# ZYNQ-Connecters.net
KiCad netlist of a schematic drawn in Altium Designer
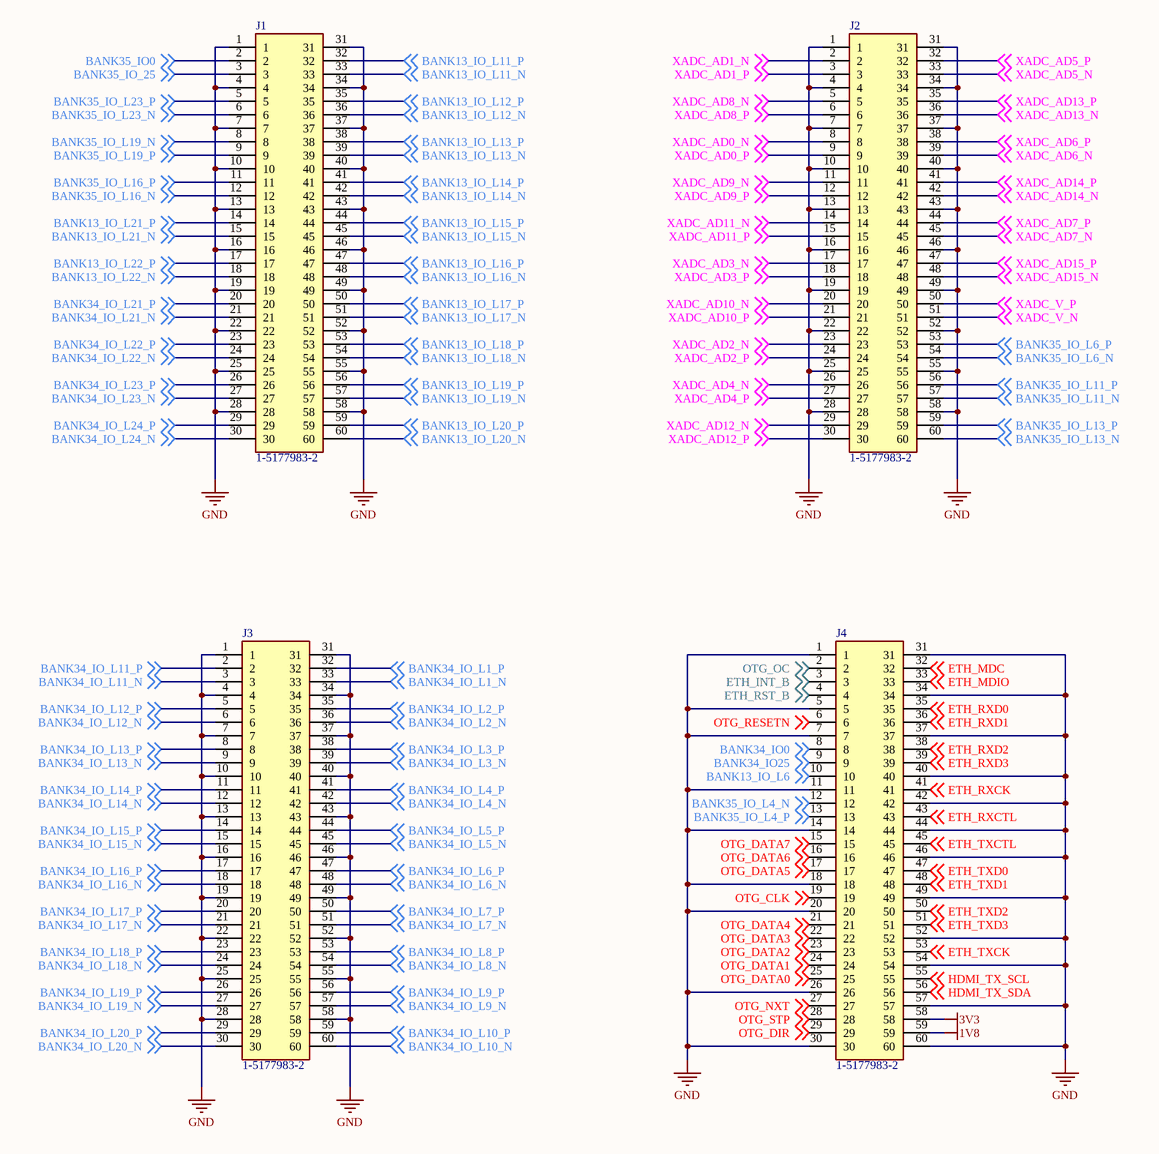
[diagram p0: ZYNQ-Connecters.SchDoc]

(export (version "E")
  (design (tool "Eeschema 10.0.6"))
  (components
    (comp (ref "J1")
      (value "1-5177983-2")
      (footprint "SamacSys:5177983-2")
      (description "Connector")
      (fields (field (name "MOUSER PART NUMBER") "571-1-5177983-2"))
      (libsource (lib "*") (part "1-5177983-2"))
    )
    (comp (ref "J2")
      (value "1-5177983-2")
      (footprint "SamacSys:5177983-2")
      (description "Connector")
      (fields (field (name "MOUSER PART NUMBER") "571-1-5177983-2"))
      (libsource (lib "*") (part "1-5177983-2"))
    )
    (comp (ref "J3")
      (value "1-5177983-2")
      (footprint "SamacSys:5177983-2")
      (description "Connector")
      (fields (field (name "MOUSER PART NUMBER") "571-1-5177983-2"))
      (libsource (lib "*") (part "1-5177983-2"))
    )
    (comp (ref "J4")
      (value "1-5177983-2")
      (footprint "SamacSys:5177983-2")
      (description "Connector")
      (fields (field (name "MOUSER PART NUMBER") "571-1-5177983-2"))
      (libsource (lib "*") (part "1-5177983-2"))
    )
  )
  (nets
    (net (code "1") (name "1V8") (class "Default")
      (node (ref "J4") (pin "59") (pinfunction "59_59") (pintype "passive"))
    )
    (net (code "2") (name "3V3") (class "Default")
      (node (ref "J4") (pin "58") (pinfunction "58_58") (pintype "passive"))
    )
    (net (code "3") (name "BANK13_IO_L6") (class "Default")
      (node (ref "J4") (pin "10") (pinfunction "10_10") (pintype "passive"))
    )
    (net (code "4") (name "BANK13_IO_L11_N") (class "Default")
      (node (ref "J1") (pin "33") (pinfunction "33_33") (pintype "passive"))
    )
    (net (code "5") (name "BANK13_IO_L11_P") (class "Default")
      (node (ref "J1") (pin "32") (pinfunction "32_32") (pintype "passive"))
    )
    (net (code "6") (name "BANK13_IO_L12_N") (class "Default")
      (node (ref "J1") (pin "36") (pinfunction "36_36") (pintype "passive"))
    )
    (net (code "7") (name "BANK13_IO_L12_P") (class "Default")
      (node (ref "J1") (pin "35") (pinfunction "35_35") (pintype "passive"))
    )
    (net (code "8") (name "BANK13_IO_L13_N") (class "Default")
      (node (ref "J1") (pin "39") (pinfunction "39_39") (pintype "passive"))
    )
    (net (code "9") (name "BANK13_IO_L13_P") (class "Default")
      (node (ref "J1") (pin "38") (pinfunction "38_38") (pintype "passive"))
    )
    (net (code "10") (name "BANK13_IO_L14_N") (class "Default")
      (node (ref "J1") (pin "42") (pinfunction "42_42") (pintype "passive"))
    )
    (net (code "11") (name "BANK13_IO_L14_P") (class "Default")
      (node (ref "J1") (pin "41") (pinfunction "41_41") (pintype "passive"))
    )
    (net (code "12") (name "BANK13_IO_L15_N") (class "Default")
      (node (ref "J1") (pin "45") (pinfunction "45_45") (pintype "passive"))
    )
    (net (code "13") (name "BANK13_IO_L15_P") (class "Default")
      (node (ref "J1") (pin "44") (pinfunction "44_44") (pintype "passive"))
    )
    (net (code "14") (name "BANK13_IO_L16_N") (class "Default")
      (node (ref "J1") (pin "48") (pinfunction "48_48") (pintype "passive"))
    )
    (net (code "15") (name "BANK13_IO_L16_P") (class "Default")
      (node (ref "J1") (pin "47") (pinfunction "47_47") (pintype "passive"))
    )
    (net (code "16") (name "BANK13_IO_L17_N") (class "Default")
      (node (ref "J1") (pin "51") (pinfunction "51_51") (pintype "passive"))
    )
    (net (code "17") (name "BANK13_IO_L17_P") (class "Default")
      (node (ref "J1") (pin "50") (pinfunction "50_50") (pintype "passive"))
    )
    (net (code "18") (name "BANK13_IO_L18_N") (class "Default")
      (node (ref "J1") (pin "54") (pinfunction "54_54") (pintype "passive"))
    )
    (net (code "19") (name "BANK13_IO_L18_P") (class "Default")
      (node (ref "J1") (pin "53") (pinfunction "53_53") (pintype "passive"))
    )
    (net (code "20") (name "BANK13_IO_L19_N") (class "Default")
      (node (ref "J1") (pin "57") (pinfunction "57_57") (pintype "passive"))
    )
    (net (code "21") (name "BANK13_IO_L19_P") (class "Default")
      (node (ref "J1") (pin "56") (pinfunction "56_56") (pintype "passive"))
    )
    (net (code "22") (name "BANK13_IO_L20_N") (class "Default")
      (node (ref "J1") (pin "60") (pinfunction "60_60") (pintype "passive"))
    )
    (net (code "23") (name "BANK13_IO_L20_P") (class "Default")
      (node (ref "J1") (pin "59") (pinfunction "59_59") (pintype "passive"))
    )
    (net (code "24") (name "BANK13_IO_L21_N") (class "Default")
      (node (ref "J1") (pin "15") (pinfunction "15_15") (pintype "passive"))
    )
    (net (code "25") (name "BANK13_IO_L21_P") (class "Default")
      (node (ref "J1") (pin "14") (pinfunction "14_14") (pintype "passive"))
    )
    (net (code "26") (name "BANK13_IO_L22_N") (class "Default")
      (node (ref "J1") (pin "18") (pinfunction "18_18") (pintype "passive"))
    )
    (net (code "27") (name "BANK13_IO_L22_P") (class "Default")
      (node (ref "J1") (pin "17") (pinfunction "17_17") (pintype "passive"))
    )
    (net (code "28") (name "BANK34_IO0") (class "Default")
      (node (ref "J4") (pin "8") (pinfunction "8_8") (pintype "passive"))
    )
    (net (code "29") (name "BANK34_IO25") (class "Default")
      (node (ref "J4") (pin "9") (pinfunction "9_9") (pintype "passive"))
    )
    (net (code "30") (name "BANK34_IO_L1_N") (class "Default")
      (node (ref "J3") (pin "33") (pinfunction "33_33") (pintype "passive"))
    )
    (net (code "31") (name "BANK34_IO_L1_P") (class "Default")
      (node (ref "J3") (pin "32") (pinfunction "32_32") (pintype "passive"))
    )
    (net (code "32") (name "BANK34_IO_L2_N") (class "Default")
      (node (ref "J3") (pin "36") (pinfunction "36_36") (pintype "passive"))
    )
    (net (code "33") (name "BANK34_IO_L2_P") (class "Default")
      (node (ref "J3") (pin "35") (pinfunction "35_35") (pintype "passive"))
    )
    (net (code "34") (name "BANK34_IO_L3_N") (class "Default")
      (node (ref "J3") (pin "39") (pinfunction "39_39") (pintype "passive"))
    )
    (net (code "35") (name "BANK34_IO_L3_P") (class "Default")
      (node (ref "J3") (pin "38") (pinfunction "38_38") (pintype "passive"))
    )
    (net (code "36") (name "BANK34_IO_L4_N") (class "Default")
      (node (ref "J3") (pin "42") (pinfunction "42_42") (pintype "passive"))
    )
    (net (code "37") (name "BANK34_IO_L4_P") (class "Default")
      (node (ref "J3") (pin "41") (pinfunction "41_41") (pintype "passive"))
    )
    (net (code "38") (name "BANK34_IO_L5_N") (class "Default")
      (node (ref "J3") (pin "45") (pinfunction "45_45") (pintype "passive"))
    )
    (net (code "39") (name "BANK34_IO_L5_P") (class "Default")
      (node (ref "J3") (pin "44") (pinfunction "44_44") (pintype "passive"))
    )
    (net (code "40") (name "BANK34_IO_L6_N") (class "Default")
      (node (ref "J3") (pin "48") (pinfunction "48_48") (pintype "passive"))
    )
    (net (code "41") (name "BANK34_IO_L6_P") (class "Default")
      (node (ref "J3") (pin "47") (pinfunction "47_47") (pintype "passive"))
    )
    (net (code "42") (name "BANK34_IO_L7_N") (class "Default")
      (node (ref "J3") (pin "51") (pinfunction "51_51") (pintype "passive"))
    )
    (net (code "43") (name "BANK34_IO_L7_P") (class "Default")
      (node (ref "J3") (pin "50") (pinfunction "50_50") (pintype "passive"))
    )
    (net (code "44") (name "BANK34_IO_L8_N") (class "Default")
      (node (ref "J3") (pin "54") (pinfunction "54_54") (pintype "passive"))
    )
    (net (code "45") (name "BANK34_IO_L8_P") (class "Default")
      (node (ref "J3") (pin "53") (pinfunction "53_53") (pintype "passive"))
    )
    (net (code "46") (name "BANK34_IO_L9_N") (class "Default")
      (node (ref "J3") (pin "57") (pinfunction "57_57") (pintype "passive"))
    )
    (net (code "47") (name "BANK34_IO_L9_P") (class "Default")
      (node (ref "J3") (pin "56") (pinfunction "56_56") (pintype "passive"))
    )
    (net (code "48") (name "BANK34_IO_L10_N") (class "Default")
      (node (ref "J3") (pin "60") (pinfunction "60_60") (pintype "passive"))
    )
    (net (code "49") (name "BANK34_IO_L10_P") (class "Default")
      (node (ref "J3") (pin "59") (pinfunction "59_59") (pintype "passive"))
    )
    (net (code "50") (name "BANK34_IO_L11_N") (class "Default")
      (node (ref "J3") (pin "3") (pinfunction "3_3") (pintype "passive"))
    )
    (net (code "51") (name "BANK34_IO_L11_P") (class "Default")
      (node (ref "J3") (pin "2") (pinfunction "2_2") (pintype "passive"))
    )
    (net (code "52") (name "BANK34_IO_L12_N") (class "Default")
      (node (ref "J3") (pin "6") (pinfunction "6_6") (pintype "passive"))
    )
    (net (code "53") (name "BANK34_IO_L12_P") (class "Default")
      (node (ref "J3") (pin "5") (pinfunction "5_5") (pintype "passive"))
    )
    (net (code "54") (name "BANK34_IO_L13_N") (class "Default")
      (node (ref "J3") (pin "9") (pinfunction "9_9") (pintype "passive"))
    )
    (net (code "55") (name "BANK34_IO_L13_P") (class "Default")
      (node (ref "J3") (pin "8") (pinfunction "8_8") (pintype "passive"))
    )
    (net (code "56") (name "BANK34_IO_L14_N") (class "Default")
      (node (ref "J3") (pin "12") (pinfunction "12_12") (pintype "passive"))
    )
    (net (code "57") (name "BANK34_IO_L14_P") (class "Default")
      (node (ref "J3") (pin "11") (pinfunction "11_11") (pintype "passive"))
    )
    (net (code "58") (name "BANK34_IO_L15_N") (class "Default")
      (node (ref "J3") (pin "15") (pinfunction "15_15") (pintype "passive"))
    )
    (net (code "59") (name "BANK34_IO_L15_P") (class "Default")
      (node (ref "J3") (pin "14") (pinfunction "14_14") (pintype "passive"))
    )
    (net (code "60") (name "BANK34_IO_L16_N") (class "Default")
      (node (ref "J3") (pin "18") (pinfunction "18_18") (pintype "passive"))
    )
    (net (code "61") (name "BANK34_IO_L16_P") (class "Default")
      (node (ref "J3") (pin "17") (pinfunction "17_17") (pintype "passive"))
    )
    (net (code "62") (name "BANK34_IO_L17_N") (class "Default")
      (node (ref "J3") (pin "21") (pinfunction "21_21") (pintype "passive"))
    )
    (net (code "63") (name "BANK34_IO_L17_P") (class "Default")
      (node (ref "J3") (pin "20") (pinfunction "20_20") (pintype "passive"))
    )
    (net (code "64") (name "BANK34_IO_L18_N") (class "Default")
      (node (ref "J3") (pin "24") (pinfunction "24_24") (pintype "passive"))
    )
    (net (code "65") (name "BANK34_IO_L18_P") (class "Default")
      (node (ref "J3") (pin "23") (pinfunction "23_23") (pintype "passive"))
    )
    (net (code "66") (name "BANK34_IO_L19_N") (class "Default")
      (node (ref "J3") (pin "27") (pinfunction "27_27") (pintype "passive"))
    )
    (net (code "67") (name "BANK34_IO_L19_P") (class "Default")
      (node (ref "J3") (pin "26") (pinfunction "26_26") (pintype "passive"))
    )
    (net (code "68") (name "BANK34_IO_L20_N") (class "Default")
      (node (ref "J3") (pin "30") (pinfunction "30_30") (pintype "passive"))
    )
    (net (code "69") (name "BANK34_IO_L20_P") (class "Default")
      (node (ref "J3") (pin "29") (pinfunction "29_29") (pintype "passive"))
    )
    (net (code "70") (name "BANK34_IO_L21_N") (class "Default")
      (node (ref "J1") (pin "21") (pinfunction "21_21") (pintype "passive"))
    )
    (net (code "71") (name "BANK34_IO_L21_P") (class "Default")
      (node (ref "J1") (pin "20") (pinfunction "20_20") (pintype "passive"))
    )
    (net (code "72") (name "BANK34_IO_L22_N") (class "Default")
      (node (ref "J1") (pin "24") (pinfunction "24_24") (pintype "passive"))
    )
    (net (code "73") (name "BANK34_IO_L22_P") (class "Default")
      (node (ref "J1") (pin "23") (pinfunction "23_23") (pintype "passive"))
    )
    (net (code "74") (name "BANK34_IO_L23_N") (class "Default")
      (node (ref "J1") (pin "27") (pinfunction "27_27") (pintype "passive"))
    )
    (net (code "75") (name "BANK34_IO_L23_P") (class "Default")
      (node (ref "J1") (pin "26") (pinfunction "26_26") (pintype "passive"))
    )
    (net (code "76") (name "BANK34_IO_L24_N") (class "Default")
      (node (ref "J1") (pin "30") (pinfunction "30_30") (pintype "passive"))
    )
    (net (code "77") (name "BANK34_IO_L24_P") (class "Default")
      (node (ref "J1") (pin "29") (pinfunction "29_29") (pintype "passive"))
    )
    (net (code "78") (name "BANK35_IO0") (class "Default")
      (node (ref "J1") (pin "2") (pinfunction "2_2") (pintype "passive"))
    )
    (net (code "79") (name "BANK35_IO_25") (class "Default")
      (node (ref "J1") (pin "3") (pinfunction "3_3") (pintype "passive"))
    )
    (net (code "80") (name "BANK35_IO_L4_N") (class "Default")
      (node (ref "J4") (pin "12") (pinfunction "12_12") (pintype "passive"))
    )
    (net (code "81") (name "BANK35_IO_L4_P") (class "Default")
      (node (ref "J4") (pin "13") (pinfunction "13_13") (pintype "passive"))
    )
    (net (code "82") (name "BANK35_IO_L6_N") (class "Default")
      (node (ref "J2") (pin "54") (pinfunction "54_54") (pintype "passive"))
    )
    (net (code "83") (name "BANK35_IO_L6_P") (class "Default")
      (node (ref "J2") (pin "53") (pinfunction "53_53") (pintype "passive"))
    )
    (net (code "84") (name "BANK35_IO_L11_N") (class "Default")
      (node (ref "J2") (pin "57") (pinfunction "57_57") (pintype "passive"))
    )
    (net (code "85") (name "BANK35_IO_L11_P") (class "Default")
      (node (ref "J2") (pin "56") (pinfunction "56_56") (pintype "passive"))
    )
    (net (code "86") (name "BANK35_IO_L13_N") (class "Default")
      (node (ref "J2") (pin "60") (pinfunction "60_60") (pintype "passive"))
    )
    (net (code "87") (name "BANK35_IO_L13_P") (class "Default")
      (node (ref "J2") (pin "59") (pinfunction "59_59") (pintype "passive"))
    )
    (net (code "88") (name "BANK35_IO_L16_N") (class "Default")
      (node (ref "J1") (pin "12") (pinfunction "12_12") (pintype "passive"))
    )
    (net (code "89") (name "BANK35_IO_L16_P") (class "Default")
      (node (ref "J1") (pin "11") (pinfunction "11_11") (pintype "passive"))
    )
    (net (code "90") (name "BANK35_IO_L19_N") (class "Default")
      (node (ref "J1") (pin "8") (pinfunction "8_8") (pintype "passive"))
    )
    (net (code "91") (name "BANK35_IO_L19_P") (class "Default")
      (node (ref "J1") (pin "9") (pinfunction "9_9") (pintype "passive"))
    )
    (net (code "92") (name "BANK35_IO_L23_N") (class "Default")
      (node (ref "J1") (pin "6") (pinfunction "6_6") (pintype "passive"))
    )
    (net (code "93") (name "BANK35_IO_L23_P") (class "Default")
      (node (ref "J1") (pin "5") (pinfunction "5_5") (pintype "passive"))
    )
    (net (code "94") (name "ETH_INT_B") (class "Default")
      (node (ref "J4") (pin "3") (pinfunction "3_3") (pintype "passive"))
    )
    (net (code "95") (name "ETH_MDC") (class "Default")
      (node (ref "J4") (pin "32") (pinfunction "32_32") (pintype "passive"))
    )
    (net (code "96") (name "ETH_MDIO") (class "Default")
      (node (ref "J4") (pin "33") (pinfunction "33_33") (pintype "passive"))
    )
    (net (code "97") (name "ETH_RST_B") (class "Default")
      (node (ref "J4") (pin "4") (pinfunction "4_4") (pintype "passive"))
    )
    (net (code "98") (name "ETH_RXCK") (class "Default")
      (node (ref "J4") (pin "41") (pinfunction "41_41") (pintype "passive"))
    )
    (net (code "99") (name "ETH_RXCTL") (class "Default")
      (node (ref "J4") (pin "43") (pinfunction "43_43") (pintype "passive"))
    )
    (net (code "100") (name "ETH_RXD0") (class "Default")
      (node (ref "J4") (pin "35") (pinfunction "35_35") (pintype "passive"))
    )
    (net (code "101") (name "ETH_RXD1") (class "Default")
      (node (ref "J4") (pin "36") (pinfunction "36_36") (pintype "passive"))
    )
    (net (code "102") (name "ETH_RXD2") (class "Default")
      (node (ref "J4") (pin "38") (pinfunction "38_38") (pintype "passive"))
    )
    (net (code "103") (name "ETH_RXD3") (class "Default")
      (node (ref "J4") (pin "39") (pinfunction "39_39") (pintype "passive"))
    )
    (net (code "104") (name "ETH_TXCK") (class "Default")
      (node (ref "J4") (pin "53") (pinfunction "53_53") (pintype "passive"))
    )
    (net (code "105") (name "ETH_TXCTL") (class "Default")
      (node (ref "J4") (pin "45") (pinfunction "45_45") (pintype "passive"))
    )
    (net (code "106") (name "ETH_TXD0") (class "Default")
      (node (ref "J4") (pin "47") (pinfunction "47_47") (pintype "passive"))
    )
    (net (code "107") (name "ETH_TXD1") (class "Default")
      (node (ref "J4") (pin "48") (pinfunction "48_48") (pintype "passive"))
    )
    (net (code "108") (name "ETH_TXD2") (class "Default")
      (node (ref "J4") (pin "50") (pinfunction "50_50") (pintype "passive"))
    )
    (net (code "109") (name "ETH_TXD3") (class "Default")
      (node (ref "J4") (pin "51") (pinfunction "51_51") (pintype "passive"))
    )
    (net (code "110") (name "GND") (class "Default")
      (node (ref "J1") (pin "1") (pinfunction "1_1") (pintype "passive"))
      (node (ref "J1") (pin "10") (pinfunction "10_10") (pintype "passive"))
      (node (ref "J1") (pin "13") (pinfunction "13_13") (pintype "passive"))
      (node (ref "J1") (pin "16") (pinfunction "16_16") (pintype "passive"))
      (node (ref "J1") (pin "19") (pinfunction "19_19") (pintype "passive"))
      (node (ref "J1") (pin "22") (pinfunction "22_22") (pintype "passive"))
      (node (ref "J1") (pin "25") (pinfunction "25_25") (pintype "passive"))
      (node (ref "J1") (pin "28") (pinfunction "28_28") (pintype "passive"))
      (node (ref "J1") (pin "31") (pinfunction "31_31") (pintype "passive"))
      (node (ref "J1") (pin "34") (pinfunction "34_34") (pintype "passive"))
      (node (ref "J1") (pin "37") (pinfunction "37_37") (pintype "passive"))
      (node (ref "J1") (pin "4") (pinfunction "4_4") (pintype "passive"))
      (node (ref "J1") (pin "40") (pinfunction "40_40") (pintype "passive"))
      (node (ref "J1") (pin "43") (pinfunction "43_43") (pintype "passive"))
      (node (ref "J1") (pin "46") (pinfunction "46_46") (pintype "passive"))
      (node (ref "J1") (pin "49") (pinfunction "49_49") (pintype "passive"))
      (node (ref "J1") (pin "52") (pinfunction "52_52") (pintype "passive"))
      (node (ref "J1") (pin "55") (pinfunction "55_55") (pintype "passive"))
      (node (ref "J1") (pin "58") (pinfunction "58_58") (pintype "passive"))
      (node (ref "J1") (pin "7") (pinfunction "7_7") (pintype "passive"))
      (node (ref "J2") (pin "1") (pinfunction "1_1") (pintype "passive"))
      (node (ref "J2") (pin "10") (pinfunction "10_10") (pintype "passive"))
      (node (ref "J2") (pin "13") (pinfunction "13_13") (pintype "passive"))
      (node (ref "J2") (pin "16") (pinfunction "16_16") (pintype "passive"))
      (node (ref "J2") (pin "19") (pinfunction "19_19") (pintype "passive"))
      (node (ref "J2") (pin "22") (pinfunction "22_22") (pintype "passive"))
      (node (ref "J2") (pin "25") (pinfunction "25_25") (pintype "passive"))
      (node (ref "J2") (pin "28") (pinfunction "28_28") (pintype "passive"))
      (node (ref "J2") (pin "31") (pinfunction "31_31") (pintype "passive"))
      (node (ref "J2") (pin "34") (pinfunction "34_34") (pintype "passive"))
      (node (ref "J2") (pin "37") (pinfunction "37_37") (pintype "passive"))
      (node (ref "J2") (pin "4") (pinfunction "4_4") (pintype "passive"))
      (node (ref "J2") (pin "40") (pinfunction "40_40") (pintype "passive"))
      (node (ref "J2") (pin "43") (pinfunction "43_43") (pintype "passive"))
      (node (ref "J2") (pin "46") (pinfunction "46_46") (pintype "passive"))
      (node (ref "J2") (pin "49") (pinfunction "49_49") (pintype "passive"))
      (node (ref "J2") (pin "52") (pinfunction "52_52") (pintype "passive"))
      (node (ref "J2") (pin "55") (pinfunction "55_55") (pintype "passive"))
      (node (ref "J2") (pin "58") (pinfunction "58_58") (pintype "passive"))
      (node (ref "J2") (pin "7") (pinfunction "7_7") (pintype "passive"))
      (node (ref "J3") (pin "1") (pinfunction "1_1") (pintype "passive"))
      (node (ref "J3") (pin "10") (pinfunction "10_10") (pintype "passive"))
      (node (ref "J3") (pin "13") (pinfunction "13_13") (pintype "passive"))
      (node (ref "J3") (pin "16") (pinfunction "16_16") (pintype "passive"))
      (node (ref "J3") (pin "19") (pinfunction "19_19") (pintype "passive"))
      (node (ref "J3") (pin "22") (pinfunction "22_22") (pintype "passive"))
      (node (ref "J3") (pin "25") (pinfunction "25_25") (pintype "passive"))
      (node (ref "J3") (pin "28") (pinfunction "28_28") (pintype "passive"))
      (node (ref "J3") (pin "31") (pinfunction "31_31") (pintype "passive"))
      (node (ref "J3") (pin "34") (pinfunction "34_34") (pintype "passive"))
      (node (ref "J3") (pin "37") (pinfunction "37_37") (pintype "passive"))
      (node (ref "J3") (pin "4") (pinfunction "4_4") (pintype "passive"))
      (node (ref "J3") (pin "40") (pinfunction "40_40") (pintype "passive"))
      (node (ref "J3") (pin "43") (pinfunction "43_43") (pintype "passive"))
      (node (ref "J3") (pin "46") (pinfunction "46_46") (pintype "passive"))
      (node (ref "J3") (pin "49") (pinfunction "49_49") (pintype "passive"))
      (node (ref "J3") (pin "52") (pinfunction "52_52") (pintype "passive"))
      (node (ref "J3") (pin "55") (pinfunction "55_55") (pintype "passive"))
      (node (ref "J3") (pin "58") (pinfunction "58_58") (pintype "passive"))
      (node (ref "J3") (pin "7") (pinfunction "7_7") (pintype "passive"))
      (node (ref "J4") (pin "1") (pinfunction "1_1") (pintype "passive"))
      (node (ref "J4") (pin "11") (pinfunction "11_11") (pintype "passive"))
      (node (ref "J4") (pin "14") (pinfunction "14_14") (pintype "passive"))
      (node (ref "J4") (pin "18") (pinfunction "18_18") (pintype "passive"))
      (node (ref "J4") (pin "20") (pinfunction "20_20") (pintype "passive"))
      (node (ref "J4") (pin "26") (pinfunction "26_26") (pintype "passive"))
      (node (ref "J4") (pin "30") (pinfunction "30_30") (pintype "passive"))
      (node (ref "J4") (pin "31") (pinfunction "31_31") (pintype "passive"))
      (node (ref "J4") (pin "34") (pinfunction "34_34") (pintype "passive"))
      (node (ref "J4") (pin "37") (pinfunction "37_37") (pintype "passive"))
      (node (ref "J4") (pin "40") (pinfunction "40_40") (pintype "passive"))
      (node (ref "J4") (pin "42") (pinfunction "42_42") (pintype "passive"))
      (node (ref "J4") (pin "44") (pinfunction "44_44") (pintype "passive"))
      (node (ref "J4") (pin "46") (pinfunction "46_46") (pintype "passive"))
      (node (ref "J4") (pin "49") (pinfunction "49_49") (pintype "passive"))
      (node (ref "J4") (pin "5") (pinfunction "5_5") (pintype "passive"))
      (node (ref "J4") (pin "52") (pinfunction "52_52") (pintype "passive"))
      (node (ref "J4") (pin "54") (pinfunction "54_54") (pintype "passive"))
      (node (ref "J4") (pin "57") (pinfunction "57_57") (pintype "passive"))
      (node (ref "J4") (pin "60") (pinfunction "60_60") (pintype "passive"))
      (node (ref "J4") (pin "7") (pinfunction "7_7") (pintype "passive"))
    )
    (net (code "111") (name "HDMI_TX_SCL") (class "Default")
      (node (ref "J4") (pin "55") (pinfunction "55_55") (pintype "passive"))
    )
    (net (code "112") (name "HDMI_TX_SDA") (class "Default")
      (node (ref "J4") (pin "56") (pinfunction "56_56") (pintype "passive"))
    )
    (net (code "113") (name "OTG_CLK") (class "Default")
      (node (ref "J4") (pin "19") (pinfunction "19_19") (pintype "passive"))
    )
    (net (code "114") (name "OTG_DATA0") (class "Default")
      (node (ref "J4") (pin "25") (pinfunction "25_25") (pintype "passive"))
    )
    (net (code "115") (name "OTG_DATA1") (class "Default")
      (node (ref "J4") (pin "24") (pinfunction "24_24") (pintype "passive"))
    )
    (net (code "116") (name "OTG_DATA2") (class "Default")
      (node (ref "J4") (pin "23") (pinfunction "23_23") (pintype "passive"))
    )
    (net (code "117") (name "OTG_DATA3") (class "Default")
      (node (ref "J4") (pin "22") (pinfunction "22_22") (pintype "passive"))
    )
    (net (code "118") (name "OTG_DATA4") (class "Default")
      (node (ref "J4") (pin "21") (pinfunction "21_21") (pintype "passive"))
    )
    (net (code "119") (name "OTG_DATA5") (class "Default")
      (node (ref "J4") (pin "17") (pinfunction "17_17") (pintype "passive"))
    )
    (net (code "120") (name "OTG_DATA6") (class "Default")
      (node (ref "J4") (pin "16") (pinfunction "16_16") (pintype "passive"))
    )
    (net (code "121") (name "OTG_DATA7") (class "Default")
      (node (ref "J4") (pin "15") (pinfunction "15_15") (pintype "passive"))
    )
    (net (code "122") (name "OTG_DIR") (class "Default")
      (node (ref "J4") (pin "29") (pinfunction "29_29") (pintype "passive"))
    )
    (net (code "123") (name "OTG_NXT") (class "Default")
      (node (ref "J4") (pin "27") (pinfunction "27_27") (pintype "passive"))
    )
    (net (code "124") (name "OTG_OC") (class "Default")
      (node (ref "J4") (pin "2") (pinfunction "2_2") (pintype "passive"))
    )
    (net (code "125") (name "OTG_RESETN") (class "Default")
      (node (ref "J4") (pin "6") (pinfunction "6_6") (pintype "passive"))
    )
    (net (code "126") (name "OTG_STP") (class "Default")
      (node (ref "J4") (pin "28") (pinfunction "28_28") (pintype "passive"))
    )
    (net (code "127") (name "XADC_AD0_N") (class "Default")
      (node (ref "J2") (pin "8") (pinfunction "8_8") (pintype "passive"))
    )
    (net (code "128") (name "XADC_AD0_P") (class "Default")
      (node (ref "J2") (pin "9") (pinfunction "9_9") (pintype "passive"))
    )
    (net (code "129") (name "XADC_AD1_N") (class "Default")
      (node (ref "J2") (pin "2") (pinfunction "2_2") (pintype "passive"))
    )
    (net (code "130") (name "XADC_AD1_P") (class "Default")
      (node (ref "J2") (pin "3") (pinfunction "3_3") (pintype "passive"))
    )
    (net (code "131") (name "XADC_AD2_N") (class "Default")
      (node (ref "J2") (pin "23") (pinfunction "23_23") (pintype "passive"))
    )
    (net (code "132") (name "XADC_AD2_P") (class "Default")
      (node (ref "J2") (pin "24") (pinfunction "24_24") (pintype "passive"))
    )
    (net (code "133") (name "XADC_AD3_N") (class "Default")
      (node (ref "J2") (pin "17") (pinfunction "17_17") (pintype "passive"))
    )
    (net (code "134") (name "XADC_AD3_P") (class "Default")
      (node (ref "J2") (pin "18") (pinfunction "18_18") (pintype "passive"))
    )
    (net (code "135") (name "XADC_AD4_N") (class "Default")
      (node (ref "J2") (pin "26") (pinfunction "26_26") (pintype "passive"))
    )
    (net (code "136") (name "XADC_AD4_P") (class "Default")
      (node (ref "J2") (pin "27") (pinfunction "27_27") (pintype "passive"))
    )
    (net (code "137") (name "XADC_AD5_N") (class "Default")
      (node (ref "J2") (pin "33") (pinfunction "33_33") (pintype "passive"))
    )
    (net (code "138") (name "XADC_AD5_P") (class "Default")
      (node (ref "J2") (pin "32") (pinfunction "32_32") (pintype "passive"))
    )
    (net (code "139") (name "XADC_AD6_N") (class "Default")
      (node (ref "J2") (pin "39") (pinfunction "39_39") (pintype "passive"))
    )
    (net (code "140") (name "XADC_AD6_P") (class "Default")
      (node (ref "J2") (pin "38") (pinfunction "38_38") (pintype "passive"))
    )
    (net (code "141") (name "XADC_AD7_N") (class "Default")
      (node (ref "J2") (pin "45") (pinfunction "45_45") (pintype "passive"))
    )
    (net (code "142") (name "XADC_AD7_P") (class "Default")
      (node (ref "J2") (pin "44") (pinfunction "44_44") (pintype "passive"))
    )
    (net (code "143") (name "XADC_AD8_N") (class "Default")
      (node (ref "J2") (pin "5") (pinfunction "5_5") (pintype "passive"))
    )
    (net (code "144") (name "XADC_AD8_P") (class "Default")
      (node (ref "J2") (pin "6") (pinfunction "6_6") (pintype "passive"))
    )
    (net (code "145") (name "XADC_AD9_N") (class "Default")
      (node (ref "J2") (pin "11") (pinfunction "11_11") (pintype "passive"))
    )
    (net (code "146") (name "XADC_AD9_P") (class "Default")
      (node (ref "J2") (pin "12") (pinfunction "12_12") (pintype "passive"))
    )
    (net (code "147") (name "XADC_AD10_N") (class "Default")
      (node (ref "J2") (pin "20") (pinfunction "20_20") (pintype "passive"))
    )
    (net (code "148") (name "XADC_AD10_P") (class "Default")
      (node (ref "J2") (pin "21") (pinfunction "21_21") (pintype "passive"))
    )
    (net (code "149") (name "XADC_AD11_N") (class "Default")
      (node (ref "J2") (pin "14") (pinfunction "14_14") (pintype "passive"))
    )
    (net (code "150") (name "XADC_AD11_P") (class "Default")
      (node (ref "J2") (pin "15") (pinfunction "15_15") (pintype "passive"))
    )
    (net (code "151") (name "XADC_AD12_N") (class "Default")
      (node (ref "J2") (pin "29") (pinfunction "29_29") (pintype "passive"))
    )
    (net (code "152") (name "XADC_AD12_P") (class "Default")
      (node (ref "J2") (pin "30") (pinfunction "30_30") (pintype "passive"))
    )
    (net (code "153") (name "XADC_AD13_N") (class "Default")
      (node (ref "J2") (pin "36") (pinfunction "36_36") (pintype "passive"))
    )
    (net (code "154") (name "XADC_AD13_P") (class "Default")
      (node (ref "J2") (pin "35") (pinfunction "35_35") (pintype "passive"))
    )
    (net (code "155") (name "XADC_AD14_N") (class "Default")
      (node (ref "J2") (pin "42") (pinfunction "42_42") (pintype "passive"))
    )
    (net (code "156") (name "XADC_AD14_P") (class "Default")
      (node (ref "J2") (pin "41") (pinfunction "41_41") (pintype "passive"))
    )
    (net (code "157") (name "XADC_AD15_N") (class "Default")
      (node (ref "J2") (pin "48") (pinfunction "48_48") (pintype "passive"))
    )
    (net (code "158") (name "XADC_AD15_P") (class "Default")
      (node (ref "J2") (pin "47") (pinfunction "47_47") (pintype "passive"))
    )
    (net (code "159") (name "XADC_V_N") (class "Default")
      (node (ref "J2") (pin "51") (pinfunction "51_51") (pintype "passive"))
    )
    (net (code "160") (name "XADC_V_P") (class "Default")
      (node (ref "J2") (pin "50") (pinfunction "50_50") (pintype "passive"))
    )
  )
)
